# Power.net
KiCad netlist of a schematic drawn in Altium Designer
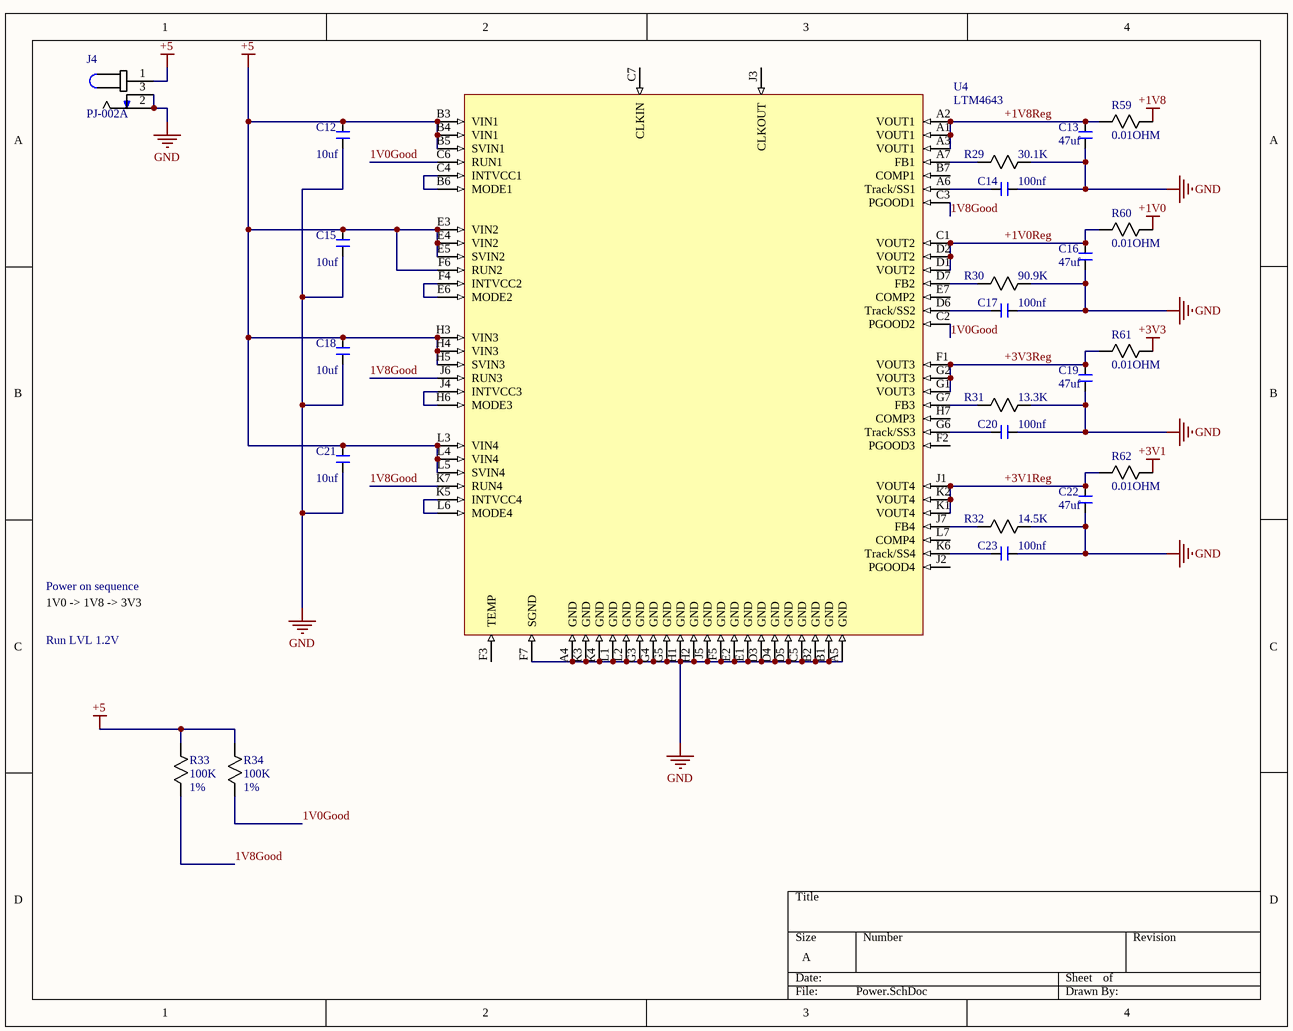
[diagram p0: Power.SchDoc]

(export (version "E")
  (design (tool "Eeschema 10.0.6"))
  (components
    (comp (ref "C12")
      (value "10uf")
      (footprint "0402Footprint")
      (description "0402")
      (libsource (lib "Capacitors") (part "10uf_0402"))
    )
    (comp (ref "C13")
      (value "47uf")
      (footprint "0805FOOTPRINT")
      (description "0805")
      (libsource (lib "Capacitors") (part "47uf_0805"))
    )
    (comp (ref "C14")
      (value "100nf")
      (footprint "0402Footprint")
      (description "0402")
      (libsource (lib "Capacitors") (part "100nf_0402"))
    )
    (comp (ref "C15")
      (value "10uf")
      (footprint "0402Footprint")
      (description "0402")
      (libsource (lib "Capacitors") (part "10uf_0402"))
    )
    (comp (ref "C16")
      (value "47uf")
      (footprint "0805FOOTPRINT")
      (description "0805")
      (libsource (lib "Capacitors") (part "47uf_0805"))
    )
    (comp (ref "C17")
      (value "100nf")
      (footprint "0402Footprint")
      (description "0402")
      (libsource (lib "Capacitors") (part "100nf_0402"))
    )
    (comp (ref "C18")
      (value "10uf")
      (footprint "0402Footprint")
      (description "0402")
      (libsource (lib "Capacitors") (part "10uf_0402"))
    )
    (comp (ref "C19")
      (value "47uf")
      (footprint "0805FOOTPRINT")
      (description "0805")
      (libsource (lib "Capacitors") (part "47uf_0805"))
    )
    (comp (ref "C20")
      (value "100nf")
      (footprint "0402Footprint")
      (description "0402")
      (libsource (lib "Capacitors") (part "100nf_0402"))
    )
    (comp (ref "C21")
      (value "10uf")
      (footprint "0402Footprint")
      (description "0402")
      (libsource (lib "Capacitors") (part "10uf_0402"))
    )
    (comp (ref "C22")
      (value "47uf")
      (footprint "0805FOOTPRINT")
      (description "0805")
      (libsource (lib "Capacitors") (part "47uf_0805"))
    )
    (comp (ref "C23")
      (value "100nf")
      (footprint "0402Footprint")
      (description "0402")
      (libsource (lib "Capacitors") (part "100nf_0402"))
    )
    (comp (ref "J4")
      (value "PJ-002A")
      (footprint "CUI_PJ-002A")
      (description "2.0 mm Center Pin, 2.5 A, Right Angle, Through Hole, Dc Power Jack Connector")
      (fields (field (name "DIGI-KEY_PART_NUMBER") "CP-002A-ND") (field (name "MF") "CUI Inc."))
      (libsource (lib "Connectors") (part "PJ-002A"))
    )
    (comp (ref "R29")
      (value "30.1K")
      (footprint "RES_CRCW_0402")
      (description "0402")
      (fields (field (name "TOLERANCE") "1%"))
      (libsource (lib "Resistors") (part "30.1K_0402"))
    )
    (comp (ref "R30")
      (value "90.9K")
      (footprint "RES_CRCW_0402")
      (description "0402")
      (fields (field (name "TOLERANCE") "1%"))
      (libsource (lib "Resistors") (part "90.9K_0402"))
    )
    (comp (ref "R31")
      (value "13.3K")
      (footprint "RES_CRCW_0402")
      (description "0402")
      (fields (field (name "TOLERANCE") "1%"))
      (libsource (lib "Resistors") (part "13.3K_0402"))
    )
    (comp (ref "R32")
      (value "14.5K")
      (footprint "RES_CRCW_0402")
      (description "0402")
      (fields (field (name "TOLERANCE") "1%"))
      (libsource (lib "Resistors") (part "14.5K_0402"))
    )
    (comp (ref "R33")
      (value "100K")
      (footprint "RES_CRCW_0402")
      (description "0402")
      (fields (field (name "TOLERANCE") "1%"))
      (libsource (lib "Resistors") (part "100K_0402"))
    )
    (comp (ref "R34")
      (value "100K")
      (footprint "RES_CRCW_0402")
      (description "0402")
      (fields (field (name "TOLERANCE") "1%"))
      (libsource (lib "Resistors") (part "100K_0402"))
    )
    (comp (ref "R59")
      (value "0.01OHM")
      (footprint "RESC1508X06N")
      (description "0603")
      (libsource (lib "Resistors") (part "0.01OHM_0603"))
    )
    (comp (ref "R60")
      (value "0.01OHM")
      (footprint "RESC1508X06N")
      (description "0603")
      (libsource (lib "Resistors") (part "0.01OHM_0603"))
    )
    (comp (ref "R61")
      (value "0.01OHM")
      (footprint "RESC1508X06N")
      (description "0603")
      (libsource (lib "Resistors") (part "0.01OHM_0603"))
    )
    (comp (ref "R62")
      (value "0.01OHM")
      (footprint "RESC1508X06N")
      (description "0603")
      (libsource (lib "Resistors") (part "0.01OHM_0603"))
    )
    (comp (ref "U4")
      (value "LTM4643")
      (footprint "LTM4643 15X9X2.42 05-08-1908")
      (libsource (lib "LTM4643") (part "LTM4643"))
    )
  )
  (nets
    (net (code "1") (name "+1V0") (class "Default")
      (node (ref "R60") (pin "1") (pinfunction "1_1") (pintype "passive"))
    )
    (net (code "2") (name "+1V8") (class "Default")
      (node (ref "R59") (pin "1") (pinfunction "1_1") (pintype "passive"))
    )
    (net (code "3") (name "+3V1") (class "Default")
      (node (ref "R62") (pin "1") (pinfunction "1_1") (pintype "passive"))
    )
    (net (code "4") (name "+3V3") (class "Default")
      (node (ref "R61") (pin "1") (pinfunction "1_1") (pintype "passive"))
    )
    (net (code "5") (name "+5") (class "Default")
      (node (ref "C12") (pin "1") (pinfunction "1_1") (pintype "passive"))
      (node (ref "C15") (pin "1") (pinfunction "1_1") (pintype "passive"))
      (node (ref "C18") (pin "1") (pinfunction "1_1") (pintype "passive"))
      (node (ref "C21") (pin "1") (pinfunction "1_1") (pintype "passive"))
      (node (ref "J4") (pin "1") (pinfunction "1_1") (pintype "passive"))
      (node (ref "R33") (pin "1") (pinfunction "1_1") (pintype "passive"))
      (node (ref "R34") (pin "1") (pinfunction "1_1") (pintype "passive"))
      (node (ref "U4") (pin "B3") (pinfunction "VIN1_B3") (pintype "input"))
      (node (ref "U4") (pin "B4") (pinfunction "VIN1_B4") (pintype "input"))
      (node (ref "U4") (pin "B5") (pinfunction "SVIN1_B5") (pintype "input"))
      (node (ref "U4") (pin "E3") (pinfunction "VIN2_E3") (pintype "input"))
      (node (ref "U4") (pin "E4") (pinfunction "VIN2_E4") (pintype "input"))
      (node (ref "U4") (pin "E5") (pinfunction "SVIN2_E5") (pintype "input"))
      (node (ref "U4") (pin "F6") (pinfunction "RUN2_F6") (pintype "input"))
      (node (ref "U4") (pin "H3") (pinfunction "VIN3_H3") (pintype "input"))
      (node (ref "U4") (pin "H4") (pinfunction "VIN3_H4") (pintype "input"))
      (node (ref "U4") (pin "H5") (pinfunction "SVIN3_H5") (pintype "input"))
      (node (ref "U4") (pin "L3") (pinfunction "VIN4_L3") (pintype "input"))
      (node (ref "U4") (pin "L4") (pinfunction "VIN4_L4") (pintype "input"))
      (node (ref "U4") (pin "L5") (pinfunction "SVIN4_L5") (pintype "input"))
    )
    (net (code "6") (name "/+1V0Reg") (class "Default")
      (node (ref "C16") (pin "2") (pinfunction "2_2") (pintype "passive"))
      (node (ref "R60") (pin "2") (pinfunction "2_2") (pintype "passive"))
      (node (ref "U4") (pin "C1") (pinfunction "VOUT2_C1") (pintype "input"))
      (node (ref "U4") (pin "D1") (pinfunction "VOUT2_D1") (pintype "input"))
      (node (ref "U4") (pin "D2") (pinfunction "VOUT2_D2") (pintype "input"))
    )
    (net (code "7") (name "/+1V8Reg") (class "Default")
      (node (ref "C13") (pin "2") (pinfunction "2_2") (pintype "passive"))
      (node (ref "R59") (pin "2") (pinfunction "2_2") (pintype "passive"))
      (node (ref "U4") (pin "A1") (pinfunction "VOUT1_A1") (pintype "input"))
      (node (ref "U4") (pin "A2") (pinfunction "VOUT1_A2") (pintype "input"))
      (node (ref "U4") (pin "A3") (pinfunction "VOUT1_A3") (pintype "input"))
    )
    (net (code "8") (name "/+3V1Reg") (class "Default")
      (node (ref "C22") (pin "2") (pinfunction "2_2") (pintype "passive"))
      (node (ref "R62") (pin "2") (pinfunction "2_2") (pintype "passive"))
      (node (ref "U4") (pin "J1") (pinfunction "VOUT4_J1") (pintype "input"))
      (node (ref "U4") (pin "K1") (pinfunction "VOUT4_K1") (pintype "input"))
      (node (ref "U4") (pin "K2") (pinfunction "VOUT4_K2") (pintype "input"))
    )
    (net (code "9") (name "/+3V3Reg") (class "Default")
      (node (ref "C19") (pin "2") (pinfunction "2_2") (pintype "passive"))
      (node (ref "R61") (pin "2") (pinfunction "2_2") (pintype "passive"))
      (node (ref "U4") (pin "F1") (pinfunction "VOUT3_F1") (pintype "input"))
      (node (ref "U4") (pin "G1") (pinfunction "VOUT3_G1") (pintype "input"))
      (node (ref "U4") (pin "G2") (pinfunction "VOUT3_G2") (pintype "input"))
    )
    (net (code "10") (name "/1V0Good") (class "Default")
      (node (ref "R34") (pin "2") (pinfunction "2_2") (pintype "passive"))
      (node (ref "U4") (pin "C2") (pinfunction "PGOOD2_C2") (pintype "input"))
      (node (ref "U4") (pin "C6") (pinfunction "RUN1_C6") (pintype "input"))
    )
    (net (code "11") (name "/1V8Good") (class "Default")
      (node (ref "R33") (pin "2") (pinfunction "2_2") (pintype "passive"))
      (node (ref "U4") (pin "C3") (pinfunction "PGOOD1_C3") (pintype "input"))
      (node (ref "U4") (pin "J6") (pinfunction "RUN3_J6") (pintype "input"))
      (node (ref "U4") (pin "K7") (pinfunction "RUN4_K7") (pintype "input"))
    )
    (net (code "12") (name "GND") (class "Default")
      (node (ref "C12") (pin "2") (pinfunction "2_2") (pintype "passive"))
      (node (ref "C13") (pin "1") (pinfunction "1_1") (pintype "passive"))
      (node (ref "C14") (pin "1") (pinfunction "1_1") (pintype "passive"))
      (node (ref "C15") (pin "2") (pinfunction "2_2") (pintype "passive"))
      (node (ref "C16") (pin "1") (pinfunction "1_1") (pintype "passive"))
      (node (ref "C17") (pin "1") (pinfunction "1_1") (pintype "passive"))
      (node (ref "C18") (pin "2") (pinfunction "2_2") (pintype "passive"))
      (node (ref "C19") (pin "1") (pinfunction "1_1") (pintype "passive"))
      (node (ref "C20") (pin "1") (pinfunction "1_1") (pintype "passive"))
      (node (ref "C21") (pin "2") (pinfunction "2_2") (pintype "passive"))
      (node (ref "C22") (pin "1") (pinfunction "1_1") (pintype "passive"))
      (node (ref "C23") (pin "1") (pinfunction "1_1") (pintype "passive"))
      (node (ref "J4") (pin "2") (pinfunction "2_2") (pintype "passive"))
      (node (ref "J4") (pin "3") (pinfunction "3_3") (pintype "passive"))
      (node (ref "R29") (pin "1") (pinfunction "1_1") (pintype "passive"))
      (node (ref "R30") (pin "1") (pinfunction "1_1") (pintype "passive"))
      (node (ref "R31") (pin "1") (pinfunction "1_1") (pintype "passive"))
      (node (ref "R32") (pin "1") (pinfunction "1_1") (pintype "passive"))
      (node (ref "U4") (pin "A4") (pinfunction "GND_A4") (pintype "input"))
      (node (ref "U4") (pin "A5") (pinfunction "GND_A5") (pintype "input"))
      (node (ref "U4") (pin "B1") (pinfunction "GND_B1") (pintype "input"))
      (node (ref "U4") (pin "B2") (pinfunction "GND_B2") (pintype "input"))
      (node (ref "U4") (pin "C5") (pinfunction "GND_C5") (pintype "input"))
      (node (ref "U4") (pin "D3") (pinfunction "GND_D3") (pintype "input"))
      (node (ref "U4") (pin "D4") (pinfunction "GND_D4") (pintype "input"))
      (node (ref "U4") (pin "D5") (pinfunction "GND_D5") (pintype "input"))
      (node (ref "U4") (pin "E1") (pinfunction "GND_E1") (pintype "input"))
      (node (ref "U4") (pin "E2") (pinfunction "GND_E2") (pintype "input"))
      (node (ref "U4") (pin "F5") (pinfunction "GND_F5") (pintype "input"))
      (node (ref "U4") (pin "F7") (pinfunction "SGND_F7") (pintype "input"))
      (node (ref "U4") (pin "G3") (pinfunction "GND_G3") (pintype "input"))
      (node (ref "U4") (pin "G4") (pinfunction "GND_G4") (pintype "input"))
      (node (ref "U4") (pin "G5") (pinfunction "GND_G5") (pintype "input"))
      (node (ref "U4") (pin "H1") (pinfunction "GND_H1") (pintype "input"))
      (node (ref "U4") (pin "H2") (pinfunction "GND_H2") (pintype "input"))
      (node (ref "U4") (pin "J5") (pinfunction "GND_J5") (pintype "input"))
      (node (ref "U4") (pin "K3") (pinfunction "GND_K3") (pintype "input"))
      (node (ref "U4") (pin "K4") (pinfunction "GND_K4") (pintype "input"))
      (node (ref "U4") (pin "L1") (pinfunction "GND_L1") (pintype "input"))
      (node (ref "U4") (pin "L2") (pinfunction "GND_L2") (pintype "input"))
    )
    (net (code "13") (name "Net-(U4-FB1)") (class "Default")
      (node (ref "R29") (pin "2") (pinfunction "2_2") (pintype "passive"))
      (node (ref "U4") (pin "A7") (pinfunction "FB1_A7") (pintype "input"))
    )
    (net (code "14") (name "Net-(U4-FB2)") (class "Default")
      (node (ref "R30") (pin "2") (pinfunction "2_2") (pintype "passive"))
      (node (ref "U4") (pin "D7") (pinfunction "FB2_D7") (pintype "input"))
    )
    (net (code "15") (name "Net-(U4-FB3)") (class "Default")
      (node (ref "R31") (pin "2") (pinfunction "2_2") (pintype "passive"))
      (node (ref "U4") (pin "G7") (pinfunction "FB3_G7") (pintype "input"))
    )
    (net (code "16") (name "Net-(U4-FB4)") (class "Default")
      (node (ref "R32") (pin "2") (pinfunction "2_2") (pintype "passive"))
      (node (ref "U4") (pin "J7") (pinfunction "FB4_J7") (pintype "input"))
    )
    (net (code "17") (name "Net-(U4-INTVCC1)") (class "Default")
      (node (ref "U4") (pin "B6") (pinfunction "MODE1_B6") (pintype "input"))
      (node (ref "U4") (pin "C4") (pinfunction "INTVCC1_C4") (pintype "input"))
    )
    (net (code "18") (name "Net-(U4-INTVCC2)") (class "Default")
      (node (ref "U4") (pin "E6") (pinfunction "MODE2_E6") (pintype "input"))
      (node (ref "U4") (pin "F4") (pinfunction "INTVCC2_F4") (pintype "input"))
    )
    (net (code "19") (name "Net-(U4-INTVCC3)") (class "Default")
      (node (ref "U4") (pin "H6") (pinfunction "MODE3_H6") (pintype "input"))
      (node (ref "U4") (pin "J4") (pinfunction "INTVCC3_J4") (pintype "input"))
    )
    (net (code "20") (name "Net-(U4-INTVCC4)") (class "Default")
      (node (ref "U4") (pin "K5") (pinfunction "INTVCC4_K5") (pintype "input"))
      (node (ref "U4") (pin "L6") (pinfunction "MODE4_L6") (pintype "input"))
    )
    (net (code "21") (name "Net-(U4-Track{slash}SS1)") (class "Default")
      (node (ref "C14") (pin "2") (pinfunction "2_2") (pintype "passive"))
      (node (ref "U4") (pin "A6") (pinfunction "Track/SS1_A6") (pintype "input"))
    )
    (net (code "22") (name "Net-(U4-Track{slash}SS2)") (class "Default")
      (node (ref "C17") (pin "2") (pinfunction "2_2") (pintype "passive"))
      (node (ref "U4") (pin "D6") (pinfunction "Track/SS2_D6") (pintype "input"))
    )
    (net (code "23") (name "Net-(U4-Track{slash}SS3)") (class "Default")
      (node (ref "C20") (pin "2") (pinfunction "2_2") (pintype "passive"))
      (node (ref "U4") (pin "G6") (pinfunction "Track/SS3_G6") (pintype "input"))
    )
    (net (code "24") (name "Net-(U4-Track{slash}SS4)") (class "Default")
      (node (ref "C23") (pin "2") (pinfunction "2_2") (pintype "passive"))
      (node (ref "U4") (pin "K6") (pinfunction "Track/SS4_K6") (pintype "input"))
    )
    (net (code "25") (name "unconnected-(U4-CLKIN-PadC7)") (class "Default")
      (node (ref "U4") (pin "C7") (pinfunction "CLKIN_C7") (pintype "input"))
    )
    (net (code "26") (name "unconnected-(U4-CLKOUT-PadJ3)") (class "Default")
      (node (ref "U4") (pin "J3") (pinfunction "CLKOUT_J3") (pintype "input"))
    )
    (net (code "27") (name "unconnected-(U4-COMP1-PadB7)") (class "Default")
      (node (ref "U4") (pin "B7") (pinfunction "COMP1_B7") (pintype "input"))
    )
    (net (code "28") (name "unconnected-(U4-COMP2-PadE7)") (class "Default")
      (node (ref "U4") (pin "E7") (pinfunction "COMP2_E7") (pintype "input"))
    )
    (net (code "29") (name "unconnected-(U4-COMP3-PadH7)") (class "Default")
      (node (ref "U4") (pin "H7") (pinfunction "COMP3_H7") (pintype "input"))
    )
    (net (code "30") (name "unconnected-(U4-COMP4-PadL7)") (class "Default")
      (node (ref "U4") (pin "L7") (pinfunction "COMP4_L7") (pintype "input"))
    )
    (net (code "31") (name "unconnected-(U4-PGOOD3-PadF2)") (class "Default")
      (node (ref "U4") (pin "F2") (pinfunction "PGOOD3_F2") (pintype "input"))
    )
    (net (code "32") (name "unconnected-(U4-PGOOD4-PadJ2)") (class "Default")
      (node (ref "U4") (pin "J2") (pinfunction "PGOOD4_J2") (pintype "input"))
    )
    (net (code "33") (name "unconnected-(U4-TEMP-PadF3)") (class "Default")
      (node (ref "U4") (pin "F3") (pinfunction "TEMP_F3") (pintype "input"))
    )
  )
)
